# PiFlash.net
KiCad netlist of a schematic drawn in EAGLE
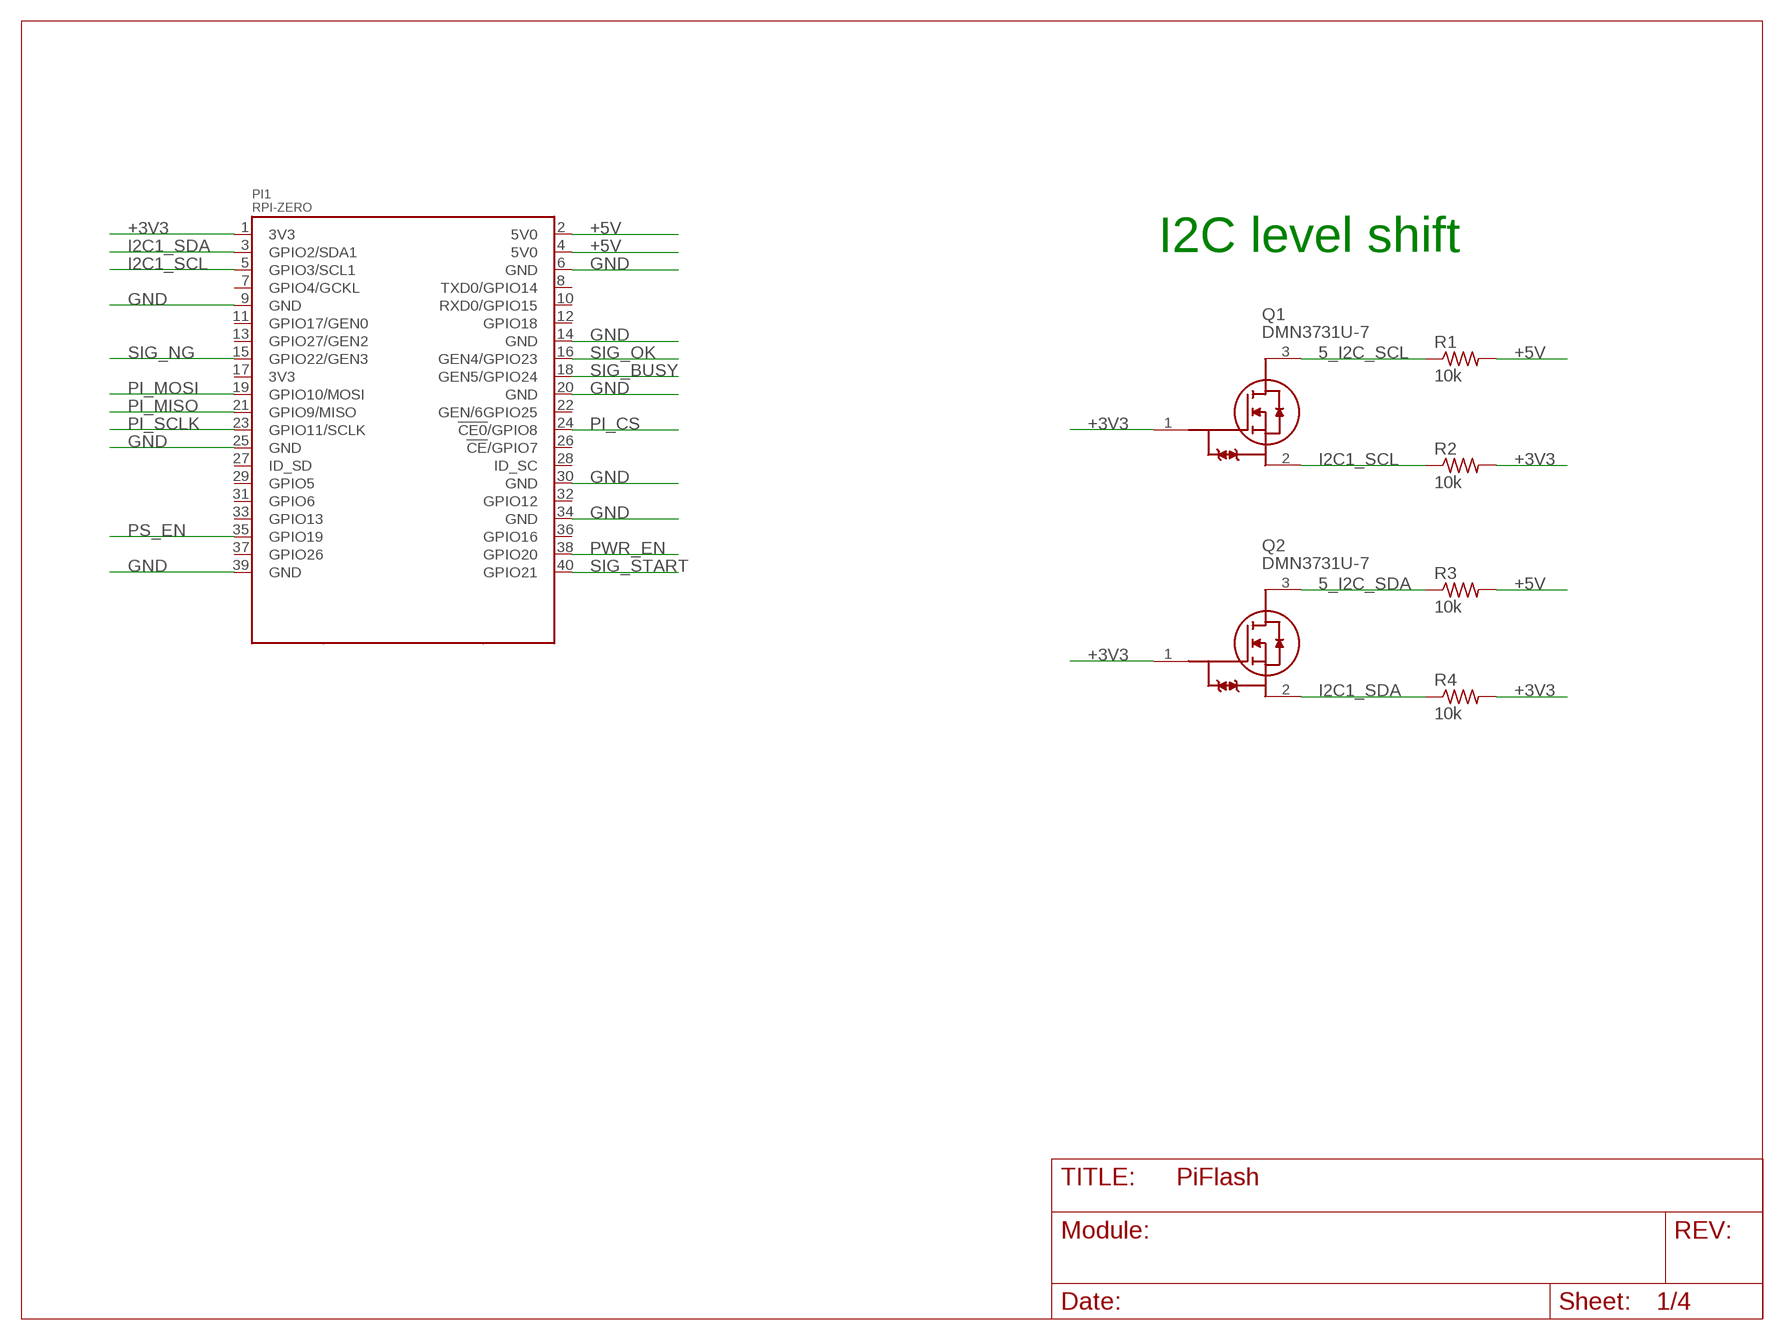
[diagram p0: schematic, sheet 1]
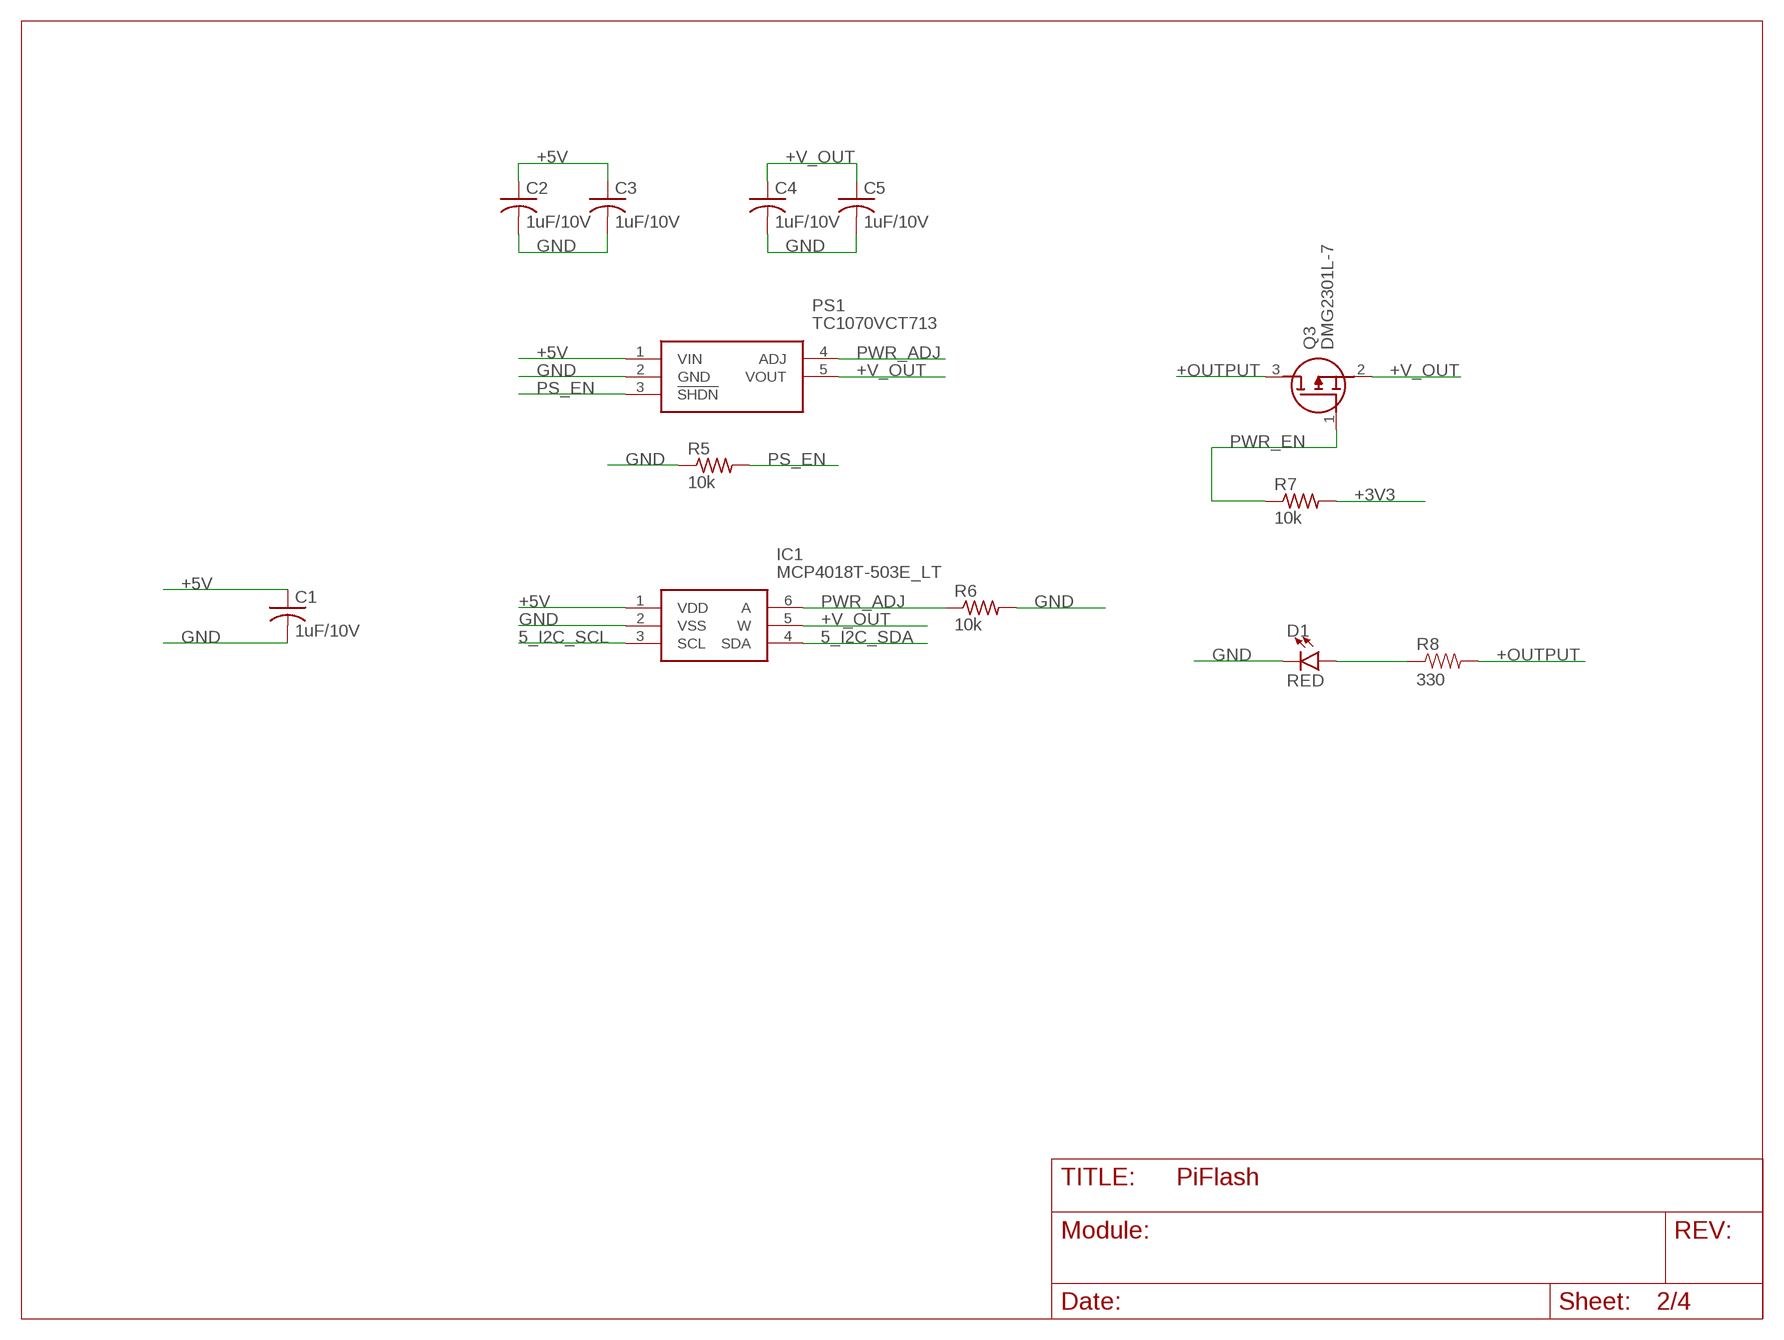
[diagram p1: schematic, sheet 2]
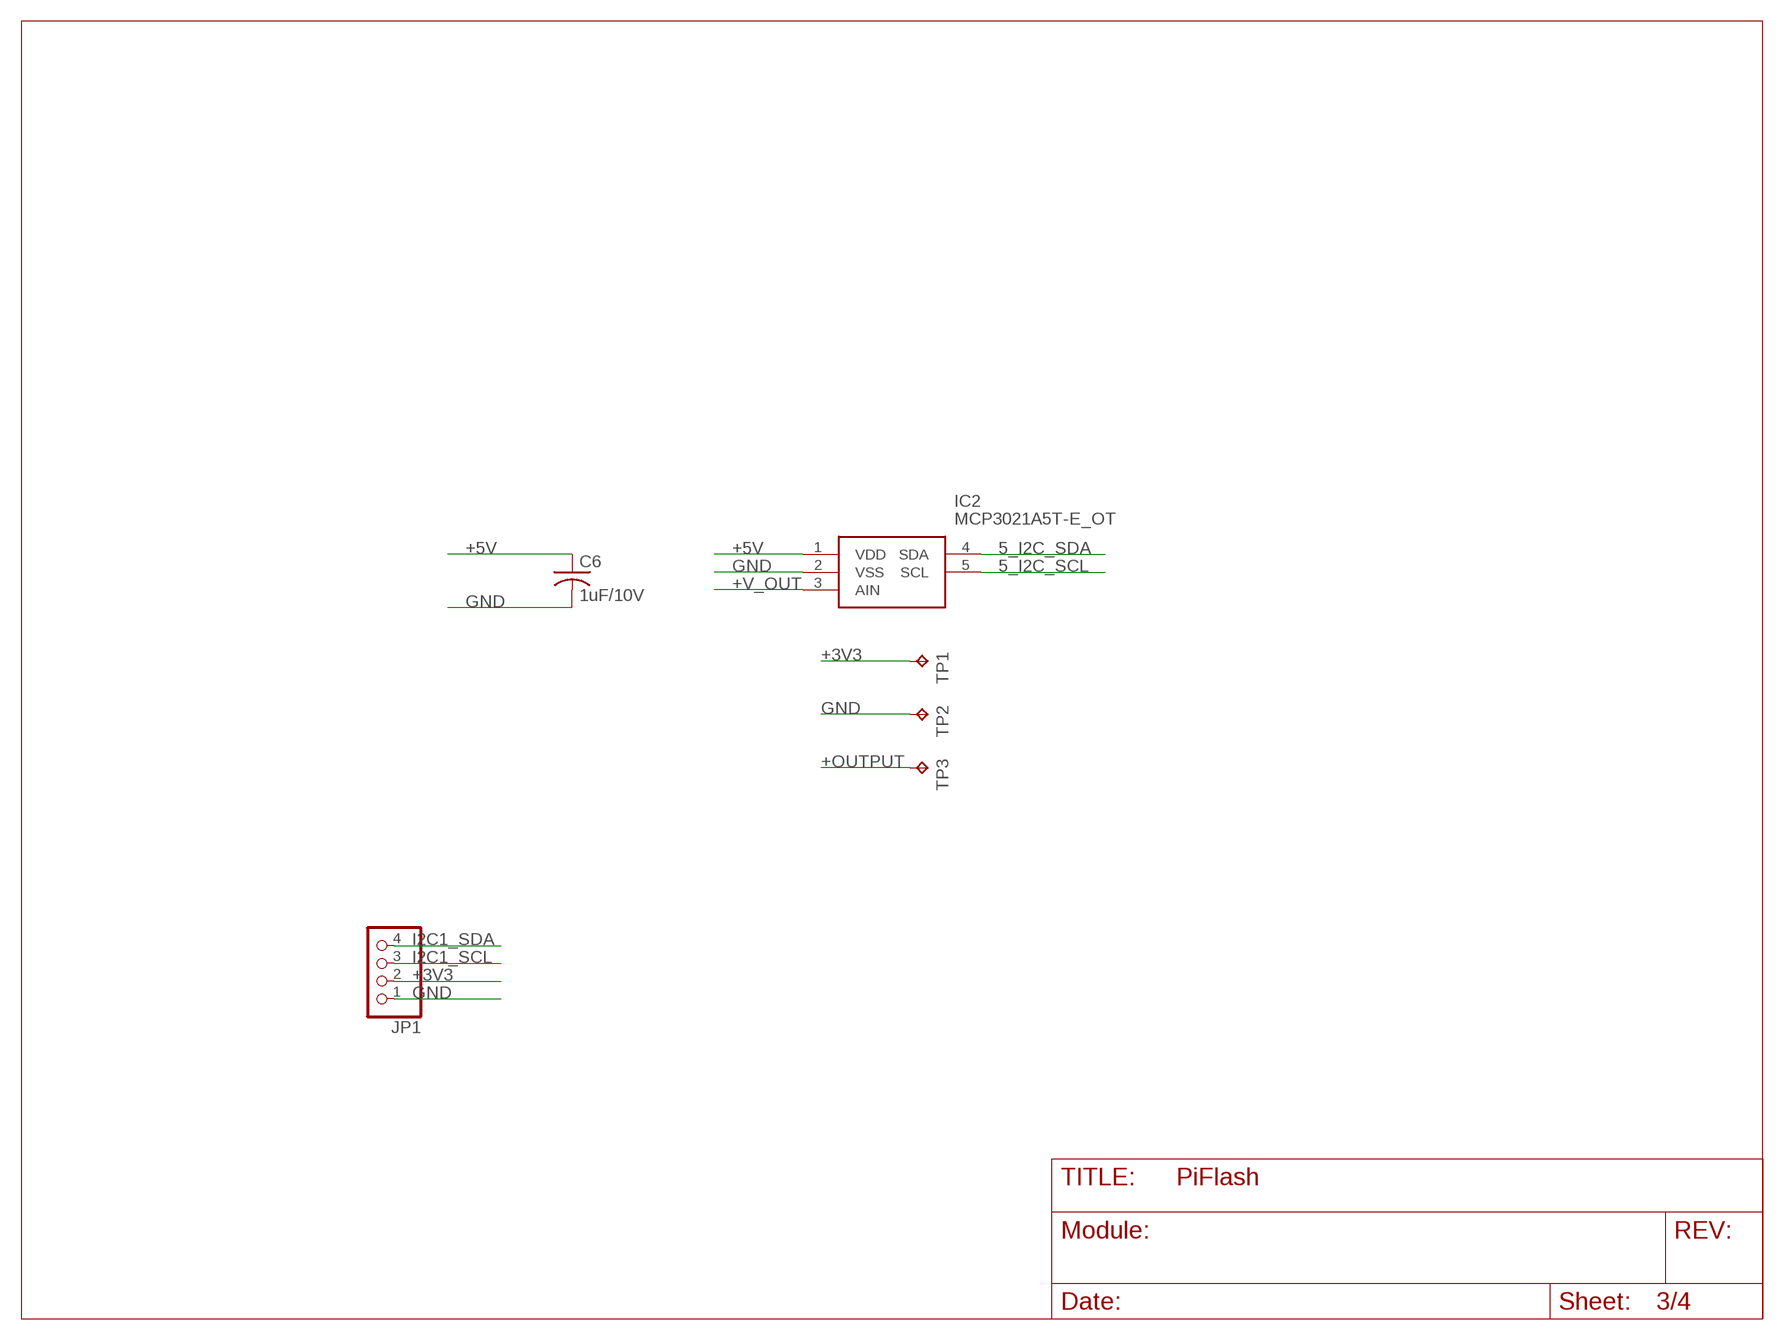
[diagram p2: schematic, sheet 3]
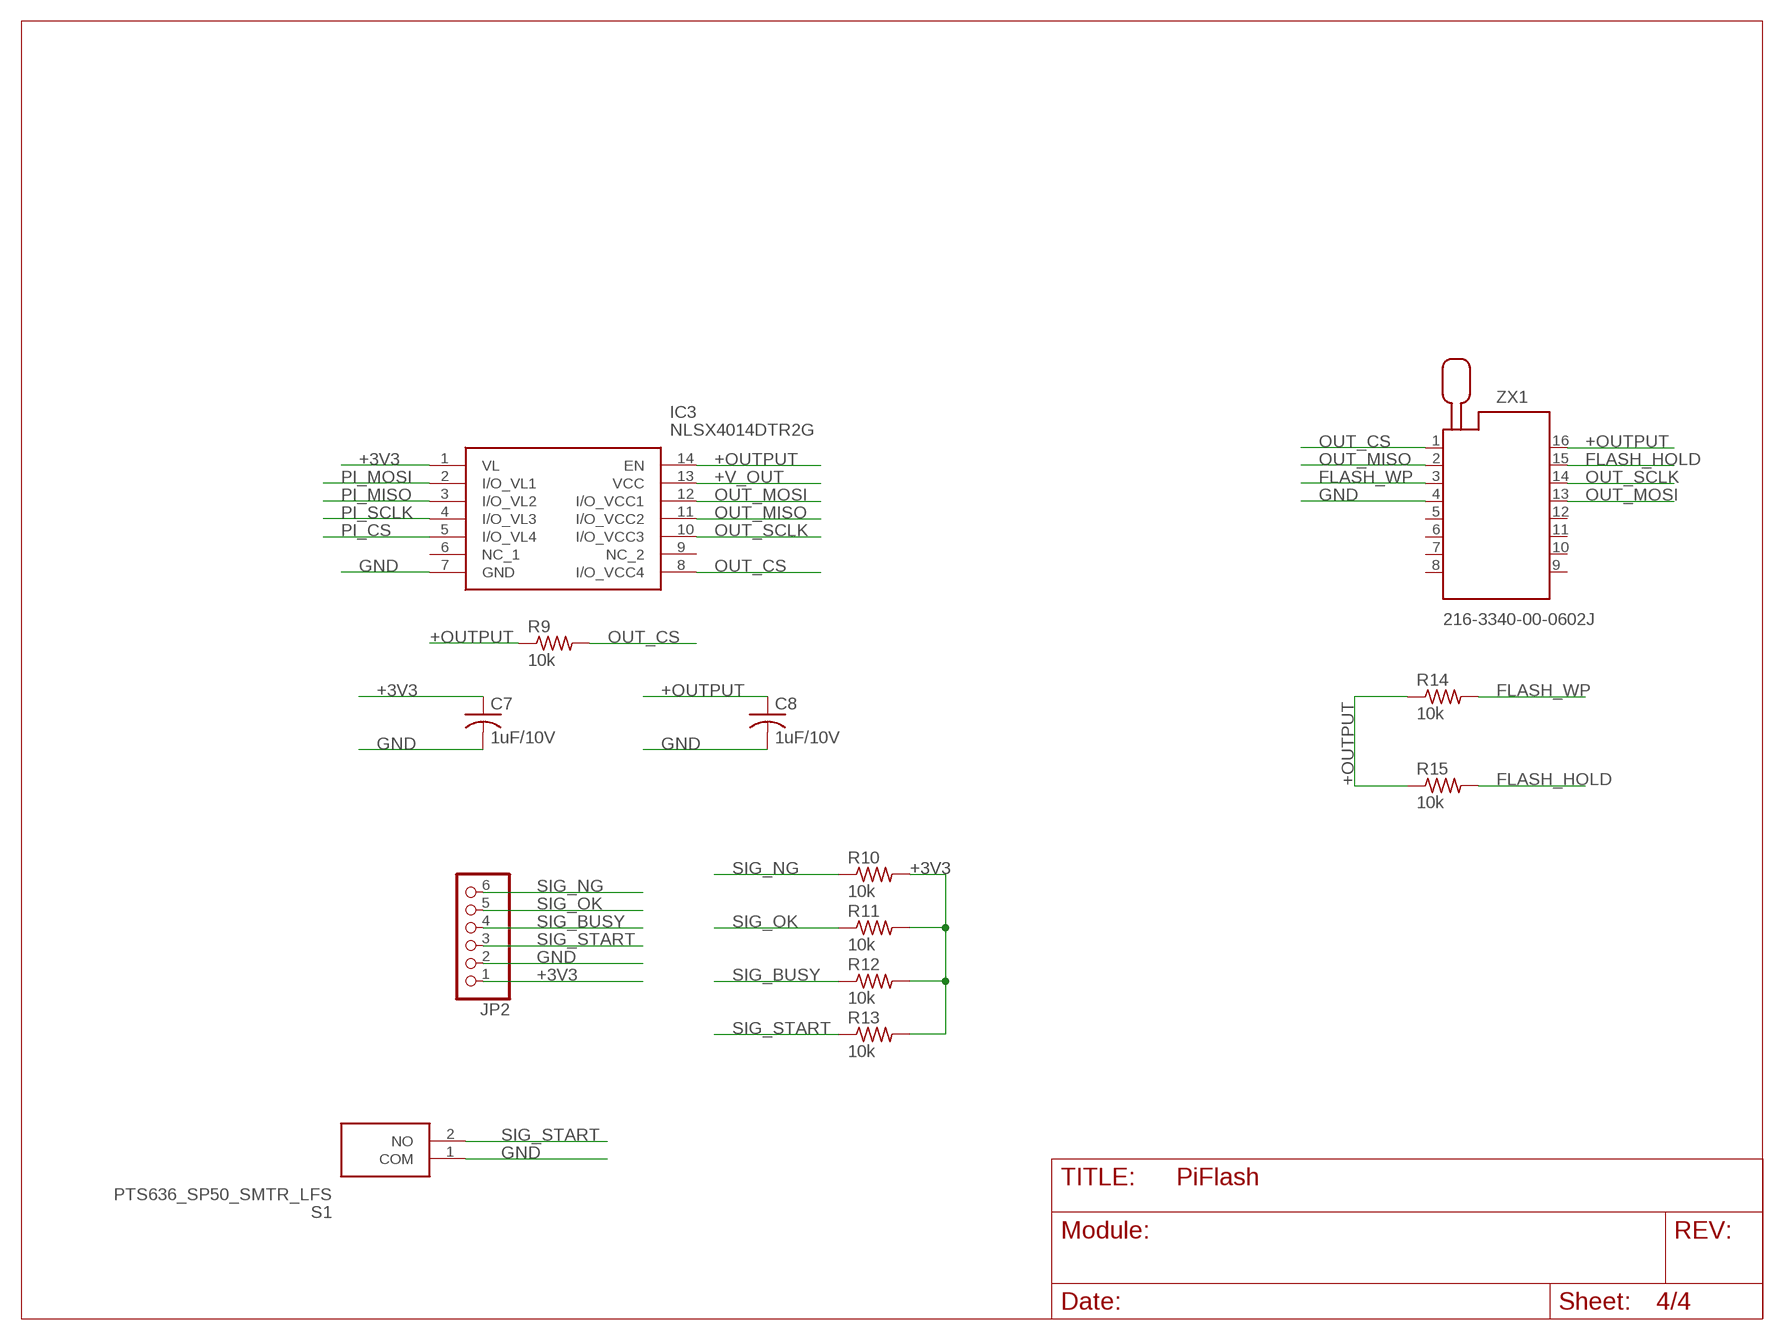
[diagram p3: schematic, sheet 4]

(export (version "E")
  (design (tool "Eeschema 10.0.6"))
  (components
    (comp (ref "C7")
      (value "1uF/10V")
      (footprint "eagle-import:C0603")
      (libsource (lib "eagle-import") (part "C-USC0603"))
    )
    (comp (ref "C8")
      (value "1uF/10V")
      (footprint "eagle-import:C0603")
      (libsource (lib "eagle-import") (part "C-USC0603"))
    )
    (comp (ref "IC3")
      (value "NLSX4014DTR2G")
      (footprint "eagle-import:SOP65P640X120-14N")
      (fields (field (name "MOUSER_PART_NUMBER") "863-NLSX4014DTR2G"))
      (libsource (lib "eagle-import") (part "NLSX4014DTR2G"))
    )
    (comp (ref "JP2")
      (value "PINHD-1X6")
      (footprint "eagle-import:1X06")
      (libsource (lib "eagle-import") (part "PINHD-1X6"))
    )
    (comp (ref "R9")
      (value "10k")
      (footprint "eagle-import:R0603")
      (libsource (lib "eagle-import") (part "R-US_R0603"))
    )
    (comp (ref "R10")
      (value "10k")
      (footprint "eagle-import:R0603")
      (libsource (lib "eagle-import") (part "R-US_R0603"))
    )
    (comp (ref "R11")
      (value "10k")
      (footprint "eagle-import:R0603")
      (libsource (lib "eagle-import") (part "R-US_R0603"))
    )
    (comp (ref "R12")
      (value "10k")
      (footprint "eagle-import:R0603")
      (libsource (lib "eagle-import") (part "R-US_R0603"))
    )
    (comp (ref "R13")
      (value "10k")
      (footprint "eagle-import:R0603")
      (libsource (lib "eagle-import") (part "R-US_R0603"))
    )
    (comp (ref "R14")
      (value "10k")
      (footprint "eagle-import:R0603")
      (libsource (lib "eagle-import") (part "R-US_R0603"))
    )
    (comp (ref "R15")
      (value "10k")
      (footprint "eagle-import:R0603")
      (libsource (lib "eagle-import") (part "R-US_R0603"))
    )
    (comp (ref "S1")
      (value "PTS636_SP50_SMTR_LFS")
      (footprint "eagle-import:PTS636SP50SMTRLFS")
      (fields
        (field (name "ARROW_PART_NUMBER") "PTS636 SP50 SMTR LFS")
        (field (name "MOUSER_PART_NUMBER") "611-PTS636SP50SMTRLF")
      )
      (libsource (lib "eagle-import") (part "PTS636_SP50_SMTR_LFS"))
    )
    (comp (ref "ZX1")
      (value "216-3340-00-0602J")
      (footprint "eagle-import:216-3340-00-0602J")
      (fields (field (name "MF") "3M"))
      (libsource (lib "eagle-import") (part "216-3340-00-0602J"))
    )
    (comp (ref "C1")
      (value "1uF/10V")
      (footprint "eagle-import:C0603")
      (libsource (lib "eagle-import") (part "C-USC0603"))
    )
    (comp (ref "C2")
      (value "1uF/10V")
      (footprint "eagle-import:C0603")
      (libsource (lib "eagle-import") (part "C-USC0603"))
    )
    (comp (ref "C3")
      (value "1uF/10V")
      (footprint "eagle-import:C0603")
      (libsource (lib "eagle-import") (part "C-USC0603"))
    )
    (comp (ref "C4")
      (value "1uF/10V")
      (footprint "eagle-import:C0603")
      (libsource (lib "eagle-import") (part "C-USC0603"))
    )
    (comp (ref "C5")
      (value "1uF/10V")
      (footprint "eagle-import:C0603")
      (libsource (lib "eagle-import") (part "C-USC0603"))
    )
    (comp (ref "D1")
      (value "RED")
      (footprint "eagle-import:LED-0402")
      (libsource (lib "eagle-import") (part "LED-RED_0402"))
    )
    (comp (ref "IC1")
      (value "MCP4018T-503E_LT")
      (footprint "eagle-import:SOT65P210X110-6N")
      (fields
        (field (name "ARROW_PART_NUMBER") "MCP4018T-503E/LT")
        (field (name "MOUSER_PART_NUMBER") "579-MCP4018T503E/LT")
      )
      (libsource (lib "eagle-import") (part "MCP4018T-503E_LT"))
    )
    (comp (ref "PS1")
      (value "TC1070VCT713")
      (footprint "eagle-import:SOT95P280X145-5N")
      (fields (field (name "MOUSER_PART_NUMBER") "579-TC1070VCT713"))
      (libsource (lib "eagle-import") (part "TC1070VCT713"))
    )
    (comp (ref "Q3")
      (value "DMG2301L-7")
      (footprint "eagle-import:SOT96P240X110-3N")
      (fields (field (name "MOUSER_PART_NUMBER") "621-DMG2301L-7"))
      (libsource (lib "eagle-import") (part "DMG2301L-7"))
    )
    (comp (ref "R5")
      (value "10k")
      (footprint "eagle-import:R0603")
      (libsource (lib "eagle-import") (part "R-US_R0603"))
    )
    (comp (ref "R6")
      (value "10k")
      (footprint "eagle-import:R0603")
      (libsource (lib "eagle-import") (part "R-US_R0603"))
    )
    (comp (ref "R7")
      (value "10k")
      (footprint "eagle-import:R0603")
      (libsource (lib "eagle-import") (part "R-US_R0603"))
    )
    (comp (ref "R8")
      (value "330")
      (footprint "eagle-import:0402")
      (libsource (lib "eagle-import") (part "RES_0402R0402"))
    )
    (comp (ref "C6")
      (value "1uF/10V")
      (footprint "eagle-import:C0603")
      (libsource (lib "eagle-import") (part "C-USC0603"))
    )
    (comp (ref "IC2")
      (value "MCP3021A5T-E_OT")
      (footprint "eagle-import:SOT95P280X145-5N")
      (fields
        (field (name "ARROW_PART_NUMBER") "MCP3021A5T-E/OT")
        (field (name "MOUSER_PART_NUMBER") "579-MCP3021A5T-E/OT")
      )
      (libsource (lib "eagle-import") (part "MCP3021A5T-E_OT"))
    )
    (comp (ref "JP1")
      (value "PINHD-1X41X04_RND")
      (footprint "eagle-import:1X04_SMALL")
      (libsource (lib "eagle-import") (part "PINHD-1X41X04_RND"))
    )
    (comp (ref "TP1")
      (value "+3v3")
      (footprint "eagle-import:TP16R")
      (libsource (lib "eagle-import") (part "TPTP16R"))
    )
    (comp (ref "TP2")
      (value "TPTP16R")
      (footprint "eagle-import:TP16R")
      (libsource (lib "eagle-import") (part "TPTP16R"))
    )
    (comp (ref "TP3")
      (value "TPTP16R")
      (footprint "eagle-import:TP16R")
      (libsource (lib "eagle-import") (part "TPTP16R"))
    )
    (comp (ref "PI1")
      (value "RPI-ZERO")
      (footprint "eagle-import:RASPBERRYPI_BASTELSTUBE_V13_RASPI_BOARD_B+_FULL")
      (libsource (lib "eagle-import") (part "RPI-ZERO"))
    )
    (comp (ref "Q1")
      (value "DMN3731U-7")
      (footprint "eagle-import:SOT96P240X110-3N")
      (fields (field (name "MOUSER_PART_NUMBER") "621-DMN3731U-7"))
      (libsource (lib "eagle-import") (part "DMN3731U-7"))
    )
    (comp (ref "Q2")
      (value "DMN3731U-7")
      (footprint "eagle-import:SOT96P240X110-3N")
      (fields (field (name "MOUSER_PART_NUMBER") "621-DMN3731U-7"))
      (libsource (lib "eagle-import") (part "DMN3731U-7"))
    )
    (comp (ref "R1")
      (value "10k")
      (footprint "eagle-import:R0603")
      (libsource (lib "eagle-import") (part "R-US_R0603"))
    )
    (comp (ref "R2")
      (value "10k")
      (footprint "eagle-import:R0603")
      (libsource (lib "eagle-import") (part "R-US_R0603"))
    )
    (comp (ref "R3")
      (value "10k")
      (footprint "eagle-import:R0603")
      (libsource (lib "eagle-import") (part "R-US_R0603"))
    )
    (comp (ref "R4")
      (value "10k")
      (footprint "eagle-import:R0603")
      (libsource (lib "eagle-import") (part "R-US_R0603"))
    )
  )
  (nets
    (net (code "1") (name "+3V3") (class "Default")
      (node (ref "C7") (pin "1") (pinfunction "1_1") (pintype "passive"))
      (node (ref "IC3") (pin "1") (pinfunction "VL_1") (pintype "bidirectional"))
      (node (ref "JP1") (pin "2") (pinfunction "2_2") (pintype "passive"))
      (node (ref "JP2") (pin "1") (pinfunction "1_1") (pintype "passive"))
      (node (ref "PI1") (pin "1") (pinfunction "3V3_1") (pintype "power_in"))
      (node (ref "Q1") (pin "1") (pinfunction "G_1") (pintype "bidirectional"))
      (node (ref "Q2") (pin "1") (pinfunction "G_1") (pintype "bidirectional"))
      (node (ref "R10") (pin "2") (pinfunction "2_2") (pintype "passive"))
      (node (ref "R11") (pin "2") (pinfunction "2_2") (pintype "passive"))
      (node (ref "R12") (pin "2") (pinfunction "2_2") (pintype "passive"))
      (node (ref "R13") (pin "2") (pinfunction "2_2") (pintype "passive"))
      (node (ref "R2") (pin "2") (pinfunction "2_2") (pintype "passive"))
      (node (ref "R4") (pin "2") (pinfunction "2_2") (pintype "passive"))
      (node (ref "R7") (pin "2") (pinfunction "2_2") (pintype "passive"))
      (node (ref "TP1") (pin "TP") (pinfunction "TP_TP") (pintype "input"))
    )
    (net (code "2") (name "+5V") (class "Default")
      (node (ref "C1") (pin "1") (pinfunction "1_1") (pintype "passive"))
      (node (ref "C2") (pin "1") (pinfunction "1_1") (pintype "passive"))
      (node (ref "C3") (pin "1") (pinfunction "1_1") (pintype "passive"))
      (node (ref "C6") (pin "1") (pinfunction "1_1") (pintype "passive"))
      (node (ref "IC1") (pin "1") (pinfunction "VDD_1") (pintype "bidirectional"))
      (node (ref "IC2") (pin "1") (pinfunction "VDD_1") (pintype "bidirectional"))
      (node (ref "PI1") (pin "2") (pinfunction "5V0_2") (pintype "power_in"))
      (node (ref "PI1") (pin "4") (pinfunction "5V0_4") (pintype "power_in"))
      (node (ref "PS1") (pin "1") (pinfunction "VIN_1") (pintype "bidirectional"))
      (node (ref "R1") (pin "2") (pinfunction "2_2") (pintype "passive"))
      (node (ref "R3") (pin "2") (pinfunction "2_2") (pintype "passive"))
    )
    (net (code "3") (name "+OUTPUT") (class "Default")
      (node (ref "C8") (pin "1") (pinfunction "1_1") (pintype "passive"))
      (node (ref "IC3") (pin "14") (pinfunction "EN_14") (pintype "bidirectional"))
      (node (ref "Q3") (pin "3") (pinfunction "D_3") (pintype "bidirectional"))
      (node (ref "R14") (pin "1") (pinfunction "1_1") (pintype "passive"))
      (node (ref "R15") (pin "1") (pinfunction "1_1") (pintype "passive"))
      (node (ref "R8") (pin "2") (pinfunction "2_2") (pintype "passive"))
      (node (ref "R9") (pin "1") (pinfunction "1_1") (pintype "passive"))
      (node (ref "TP3") (pin "TP") (pinfunction "TP_TP") (pintype "input"))
      (node (ref "ZX1") (pin "16") (pinfunction "16_16") (pintype "passive"))
    )
    (net (code "4") (name "+V_OUT") (class "Default")
      (node (ref "C4") (pin "1") (pinfunction "1_1") (pintype "passive"))
      (node (ref "C5") (pin "1") (pinfunction "1_1") (pintype "passive"))
      (node (ref "IC1") (pin "5") (pinfunction "W_5") (pintype "bidirectional"))
      (node (ref "IC2") (pin "3") (pinfunction "AIN_3") (pintype "bidirectional"))
      (node (ref "IC3") (pin "13") (pinfunction "VCC_13") (pintype "bidirectional"))
      (node (ref "PS1") (pin "5") (pinfunction "VOUT_5") (pintype "bidirectional"))
      (node (ref "Q3") (pin "2") (pinfunction "S_2") (pintype "bidirectional"))
    )
    (net (code "5") (name "3V3") (class "Default")
      (node (ref "PI1") (pin "17") (pinfunction "3V3_17") (pintype "power_in"))
    )
    (net (code "6") (name "5_I2C_SCL") (class "Default")
      (node (ref "IC1") (pin "3") (pinfunction "SCL_3") (pintype "bidirectional"))
      (node (ref "IC2") (pin "5") (pinfunction "SCL_5") (pintype "bidirectional"))
      (node (ref "Q1") (pin "3") (pinfunction "D_3") (pintype "bidirectional"))
      (node (ref "R1") (pin "1") (pinfunction "1_1") (pintype "passive"))
    )
    (net (code "7") (name "5_I2C_SDA") (class "Default")
      (node (ref "IC1") (pin "4") (pinfunction "SDA_4") (pintype "bidirectional"))
      (node (ref "IC2") (pin "4") (pinfunction "SDA_4") (pintype "bidirectional"))
      (node (ref "Q2") (pin "3") (pinfunction "D_3") (pintype "bidirectional"))
      (node (ref "R3") (pin "1") (pinfunction "1_1") (pintype "passive"))
    )
    (net (code "8") (name "FLASH_HOLD") (class "Default")
      (node (ref "R15") (pin "2") (pinfunction "2_2") (pintype "passive"))
      (node (ref "ZX1") (pin "15") (pinfunction "15_15") (pintype "passive"))
    )
    (net (code "9") (name "FLASH_WP") (class "Default")
      (node (ref "R14") (pin "2") (pinfunction "2_2") (pintype "passive"))
      (node (ref "ZX1") (pin "3") (pinfunction "3_3") (pintype "passive"))
    )
    (net (code "10") (name "GND") (class "Default")
      (node (ref "C1") (pin "2") (pinfunction "2_2") (pintype "passive"))
      (node (ref "C2") (pin "2") (pinfunction "2_2") (pintype "passive"))
      (node (ref "C3") (pin "2") (pinfunction "2_2") (pintype "passive"))
      (node (ref "C4") (pin "2") (pinfunction "2_2") (pintype "passive"))
      (node (ref "C5") (pin "2") (pinfunction "2_2") (pintype "passive"))
      (node (ref "C6") (pin "2") (pinfunction "2_2") (pintype "passive"))
      (node (ref "C7") (pin "2") (pinfunction "2_2") (pintype "passive"))
      (node (ref "C8") (pin "2") (pinfunction "2_2") (pintype "passive"))
      (node (ref "D1") (pin "C") (pinfunction "C_C") (pintype "passive"))
      (node (ref "IC1") (pin "2") (pinfunction "VSS_2") (pintype "bidirectional"))
      (node (ref "IC2") (pin "2") (pinfunction "VSS_2") (pintype "bidirectional"))
      (node (ref "IC3") (pin "7") (pinfunction "GND_7") (pintype "bidirectional"))
      (node (ref "JP1") (pin "1") (pinfunction "1_1") (pintype "passive"))
      (node (ref "JP2") (pin "2") (pinfunction "2_2") (pintype "passive"))
      (node (ref "PI1") (pin "14") (pinfunction "GND_14") (pintype "power_in"))
      (node (ref "PI1") (pin "20") (pinfunction "GND_20") (pintype "power_in"))
      (node (ref "PI1") (pin "25") (pinfunction "GND_25") (pintype "power_in"))
      (node (ref "PI1") (pin "30") (pinfunction "GND_30") (pintype "power_in"))
      (node (ref "PI1") (pin "34") (pinfunction "GND_34") (pintype "power_in"))
      (node (ref "PI1") (pin "39") (pinfunction "GND_39") (pintype "power_in"))
      (node (ref "PI1") (pin "6") (pinfunction "GND_6") (pintype "power_in"))
      (node (ref "PI1") (pin "9") (pinfunction "GND_9") (pintype "power_in"))
      (node (ref "PS1") (pin "2") (pinfunction "GND_2") (pintype "bidirectional"))
      (node (ref "R5") (pin "1") (pinfunction "1_1") (pintype "passive"))
      (node (ref "R6") (pin "2") (pinfunction "2_2") (pintype "passive"))
      (node (ref "S1") (pin "1") (pinfunction "COM_1") (pintype "bidirectional"))
      (node (ref "TP2") (pin "TP") (pinfunction "TP_TP") (pintype "input"))
      (node (ref "ZX1") (pin "4") (pinfunction "4_4") (pintype "passive"))
    )
    (net (code "11") (name "I2C1_SCL") (class "Default")
      (node (ref "JP1") (pin "3") (pinfunction "3_3") (pintype "passive"))
      (node (ref "PI1") (pin "5") (pinfunction "GPIO3/SCL1_5") (pintype "bidirectional"))
      (node (ref "Q1") (pin "2") (pinfunction "S_2") (pintype "bidirectional"))
      (node (ref "R2") (pin "1") (pinfunction "1_1") (pintype "passive"))
    )
    (net (code "12") (name "I2C1_SDA") (class "Default")
      (node (ref "JP1") (pin "4") (pinfunction "4_4") (pintype "passive"))
      (node (ref "PI1") (pin "3") (pinfunction "GPIO2/SDA1_3") (pintype "bidirectional"))
      (node (ref "Q2") (pin "2") (pinfunction "S_2") (pintype "bidirectional"))
      (node (ref "R4") (pin "1") (pinfunction "1_1") (pintype "passive"))
    )
    (net (code "13") (name "Net-(D1-PadA)") (class "Default")
      (node (ref "D1") (pin "A") (pinfunction "A_A") (pintype "passive"))
      (node (ref "R8") (pin "1") (pinfunction "1_1") (pintype "passive"))
    )
    (net (code "14") (name "OUT_CS") (class "Default")
      (node (ref "IC3") (pin "8") (pinfunction "I/O_VCC4_8") (pintype "bidirectional"))
      (node (ref "R9") (pin "2") (pinfunction "2_2") (pintype "passive"))
      (node (ref "ZX1") (pin "1") (pinfunction "1_1") (pintype "passive"))
    )
    (net (code "15") (name "OUT_MISO") (class "Default")
      (node (ref "IC3") (pin "11") (pinfunction "I/O_VCC2_11") (pintype "bidirectional"))
      (node (ref "ZX1") (pin "2") (pinfunction "2_2") (pintype "passive"))
    )
    (net (code "16") (name "OUT_MOSI") (class "Default")
      (node (ref "IC3") (pin "12") (pinfunction "I/O_VCC1_12") (pintype "bidirectional"))
      (node (ref "ZX1") (pin "13") (pinfunction "13_13") (pintype "passive"))
    )
    (net (code "17") (name "OUT_SCLK") (class "Default")
      (node (ref "IC3") (pin "10") (pinfunction "I/O_VCC3_10") (pintype "bidirectional"))
      (node (ref "ZX1") (pin "14") (pinfunction "14_14") (pintype "passive"))
    )
    (net (code "18") (name "PI_CS") (class "Default")
      (node (ref "IC3") (pin "5") (pinfunction "I/O_VL4_5") (pintype "bidirectional"))
      (node (ref "PI1") (pin "24") (pinfunction "~{CE0}/GPIO8_24") (pintype "bidirectional"))
    )
    (net (code "19") (name "PI_MISO") (class "Default")
      (node (ref "IC3") (pin "3") (pinfunction "I/O_VL2_3") (pintype "bidirectional"))
      (node (ref "PI1") (pin "21") (pinfunction "GPIO9/MISO_21") (pintype "bidirectional"))
    )
    (net (code "20") (name "PI_MOSI") (class "Default")
      (node (ref "IC3") (pin "2") (pinfunction "I/O_VL1_2") (pintype "bidirectional"))
      (node (ref "PI1") (pin "19") (pinfunction "GPIO10/MOSI_19") (pintype "bidirectional"))
    )
    (net (code "21") (name "PI_SCLK") (class "Default")
      (node (ref "IC3") (pin "4") (pinfunction "I/O_VL3_4") (pintype "bidirectional"))
      (node (ref "PI1") (pin "23") (pinfunction "GPIO11/SCLK_23") (pintype "bidirectional"))
    )
    (net (code "22") (name "PS_EN") (class "Default")
      (node (ref "PI1") (pin "35") (pinfunction "GPIO19_35") (pintype "bidirectional"))
      (node (ref "PS1") (pin "3") (pinfunction "~{SHDN}_3") (pintype "bidirectional"))
      (node (ref "R5") (pin "2") (pinfunction "2_2") (pintype "passive"))
    )
    (net (code "23") (name "PWR_ADJ") (class "Default")
      (node (ref "IC1") (pin "6") (pinfunction "A_6") (pintype "bidirectional"))
      (node (ref "PS1") (pin "4") (pinfunction "ADJ_4") (pintype "bidirectional"))
      (node (ref "R6") (pin "1") (pinfunction "1_1") (pintype "passive"))
    )
    (net (code "24") (name "PWR_EN") (class "Default")
      (node (ref "PI1") (pin "38") (pinfunction "GPIO20_38") (pintype "bidirectional"))
      (node (ref "Q3") (pin "1") (pinfunction "G_1") (pintype "bidirectional"))
      (node (ref "R7") (pin "1") (pinfunction "1_1") (pintype "passive"))
    )
    (net (code "25") (name "SIG_BUSY") (class "Default")
      (node (ref "JP2") (pin "4") (pinfunction "4_4") (pintype "passive"))
      (node (ref "PI1") (pin "18") (pinfunction "GEN5/GPIO24_18") (pintype "bidirectional"))
      (node (ref "R12") (pin "1") (pinfunction "1_1") (pintype "passive"))
    )
    (net (code "26") (name "SIG_NG") (class "Default")
      (node (ref "JP2") (pin "6") (pinfunction "6_6") (pintype "passive"))
      (node (ref "PI1") (pin "15") (pinfunction "GPIO22/GEN3_15") (pintype "bidirectional"))
      (node (ref "R10") (pin "1") (pinfunction "1_1") (pintype "passive"))
    )
    (net (code "27") (name "SIG_OK") (class "Default")
      (node (ref "JP2") (pin "5") (pinfunction "5_5") (pintype "passive"))
      (node (ref "PI1") (pin "16") (pinfunction "GEN4/GPIO23_16") (pintype "bidirectional"))
      (node (ref "R11") (pin "1") (pinfunction "1_1") (pintype "passive"))
    )
    (net (code "28") (name "SIG_START") (class "Default")
      (node (ref "JP2") (pin "3") (pinfunction "3_3") (pintype "passive"))
      (node (ref "PI1") (pin "40") (pinfunction "GPIO21_40") (pintype "bidirectional"))
      (node (ref "R13") (pin "1") (pinfunction "1_1") (pintype "passive"))
      (node (ref "S1") (pin "2") (pinfunction "NO_2") (pintype "bidirectional"))
    )
    (net (code "29") (name "unconnected-(IC3-NC_1-Pad6)") (class "Default")
      (node (ref "IC3") (pin "6") (pinfunction "NC_1_6") (pintype "bidirectional"))
    )
    (net (code "30") (name "unconnected-(IC3-NC_2-Pad9)") (class "Default")
      (node (ref "IC3") (pin "9") (pinfunction "NC_2_9") (pintype "bidirectional"))
    )
    (net (code "31") (name "unconnected-(PI1-GEN{slash}6GPIO25-Pad22)") (class "Default")
      (node (ref "PI1") (pin "22") (pinfunction "GEN/6GPIO25_22") (pintype "bidirectional"))
    )
    (net (code "32") (name "unconnected-(PI1-GPIO4{slash}GCKL-Pad7)") (class "Default")
      (node (ref "PI1") (pin "7") (pinfunction "GPIO4/GCKL_7") (pintype "bidirectional"))
    )
    (net (code "33") (name "unconnected-(PI1-GPIO5-Pad29)") (class "Default")
      (node (ref "PI1") (pin "29") (pinfunction "GPIO5_29") (pintype "bidirectional"))
    )
    (net (code "34") (name "unconnected-(PI1-GPIO6-Pad31)") (class "Default")
      (node (ref "PI1") (pin "31") (pinfunction "GPIO6_31") (pintype "bidirectional"))
    )
    (net (code "35") (name "unconnected-(PI1-GPIO12-Pad32)") (class "Default")
      (node (ref "PI1") (pin "32") (pinfunction "GPIO12_32") (pintype "bidirectional"))
    )
    (net (code "36") (name "unconnected-(PI1-GPIO13-Pad33)") (class "Default")
      (node (ref "PI1") (pin "33") (pinfunction "GPIO13_33") (pintype "bidirectional"))
    )
    (net (code "37") (name "unconnected-(PI1-GPIO16-Pad36)") (class "Default")
      (node (ref "PI1") (pin "36") (pinfunction "GPIO16_36") (pintype "bidirectional"))
    )
    (net (code "38") (name "unconnected-(PI1-GPIO17{slash}GEN0-Pad11)") (class "Default")
      (node (ref "PI1") (pin "11") (pinfunction "GPIO17/GEN0_11") (pintype "bidirectional"))
    )
    (net (code "39") (name "unconnected-(PI1-GPIO18-Pad12)") (class "Default")
      (node (ref "PI1") (pin "12") (pinfunction "GPIO18_12") (pintype "bidirectional"))
    )
    (net (code "40") (name "unconnected-(PI1-GPIO26-Pad37)") (class "Default")
      (node (ref "PI1") (pin "37") (pinfunction "GPIO26_37") (pintype "bidirectional"))
    )
    (net (code "41") (name "unconnected-(PI1-GPIO27{slash}GEN2-Pad13)") (class "Default")
      (node (ref "PI1") (pin "13") (pinfunction "GPIO27/GEN2_13") (pintype "bidirectional"))
    )
    (net (code "42") (name "unconnected-(PI1-ID_SC-Pad28)") (class "Default")
      (node (ref "PI1") (pin "28") (pinfunction "ID_SC_28") (pintype "bidirectional"))
    )
    (net (code "43") (name "unconnected-(PI1-ID_SD-Pad27)") (class "Default")
      (node (ref "PI1") (pin "27") (pinfunction "ID_SD_27") (pintype "bidirectional"))
    )
    (net (code "44") (name "unconnected-(PI1-RXD0{slash}GPIO15-Pad10)") (class "Default")
      (node (ref "PI1") (pin "10") (pinfunction "RXD0/GPIO15_10") (pintype "bidirectional"))
    )
    (net (code "45") (name "unconnected-(PI1-TXD0{slash}GPIO14-Pad8)") (class "Default")
      (node (ref "PI1") (pin "8") (pinfunction "TXD0/GPIO14_8") (pintype "bidirectional"))
    )
    (net (code "46") (name "unconnected-(PI1-~{CE}{slash}GPIO7-Pad26)") (class "Default")
      (node (ref "PI1") (pin "26") (pinfunction "~{CE}/GPIO7_26") (pintype "bidirectional"))
    )
    (net (code "47") (name "unconnected-(ZX1-Pad5)") (class "Default")
      (node (ref "ZX1") (pin "5") (pinfunction "5_5") (pintype "passive"))
    )
    (net (code "48") (name "unconnected-(ZX1-Pad6)") (class "Default")
      (node (ref "ZX1") (pin "6") (pinfunction "6_6") (pintype "passive"))
    )
    (net (code "49") (name "unconnected-(ZX1-Pad7)") (class "Default")
      (node (ref "ZX1") (pin "7") (pinfunction "7_7") (pintype "passive"))
    )
    (net (code "50") (name "unconnected-(ZX1-Pad8)") (class "Default")
      (node (ref "ZX1") (pin "8") (pinfunction "8_8") (pintype "passive"))
    )
    (net (code "51") (name "unconnected-(ZX1-Pad9)") (class "Default")
      (node (ref "ZX1") (pin "9") (pinfunction "9_9") (pintype "passive"))
    )
    (net (code "52") (name "unconnected-(ZX1-Pad10)") (class "Default")
      (node (ref "ZX1") (pin "10") (pinfunction "10_10") (pintype "passive"))
    )
    (net (code "53") (name "unconnected-(ZX1-Pad11)") (class "Default")
      (node (ref "ZX1") (pin "11") (pinfunction "11_11") (pintype "passive"))
    )
    (net (code "54") (name "unconnected-(ZX1-Pad12)") (class "Default")
      (node (ref "ZX1") (pin "12") (pinfunction "12_12") (pintype "passive"))
    )
  )
)
